# CamelDox_Sch.net
KiCad netlist of a schematic drawn in EAGLE
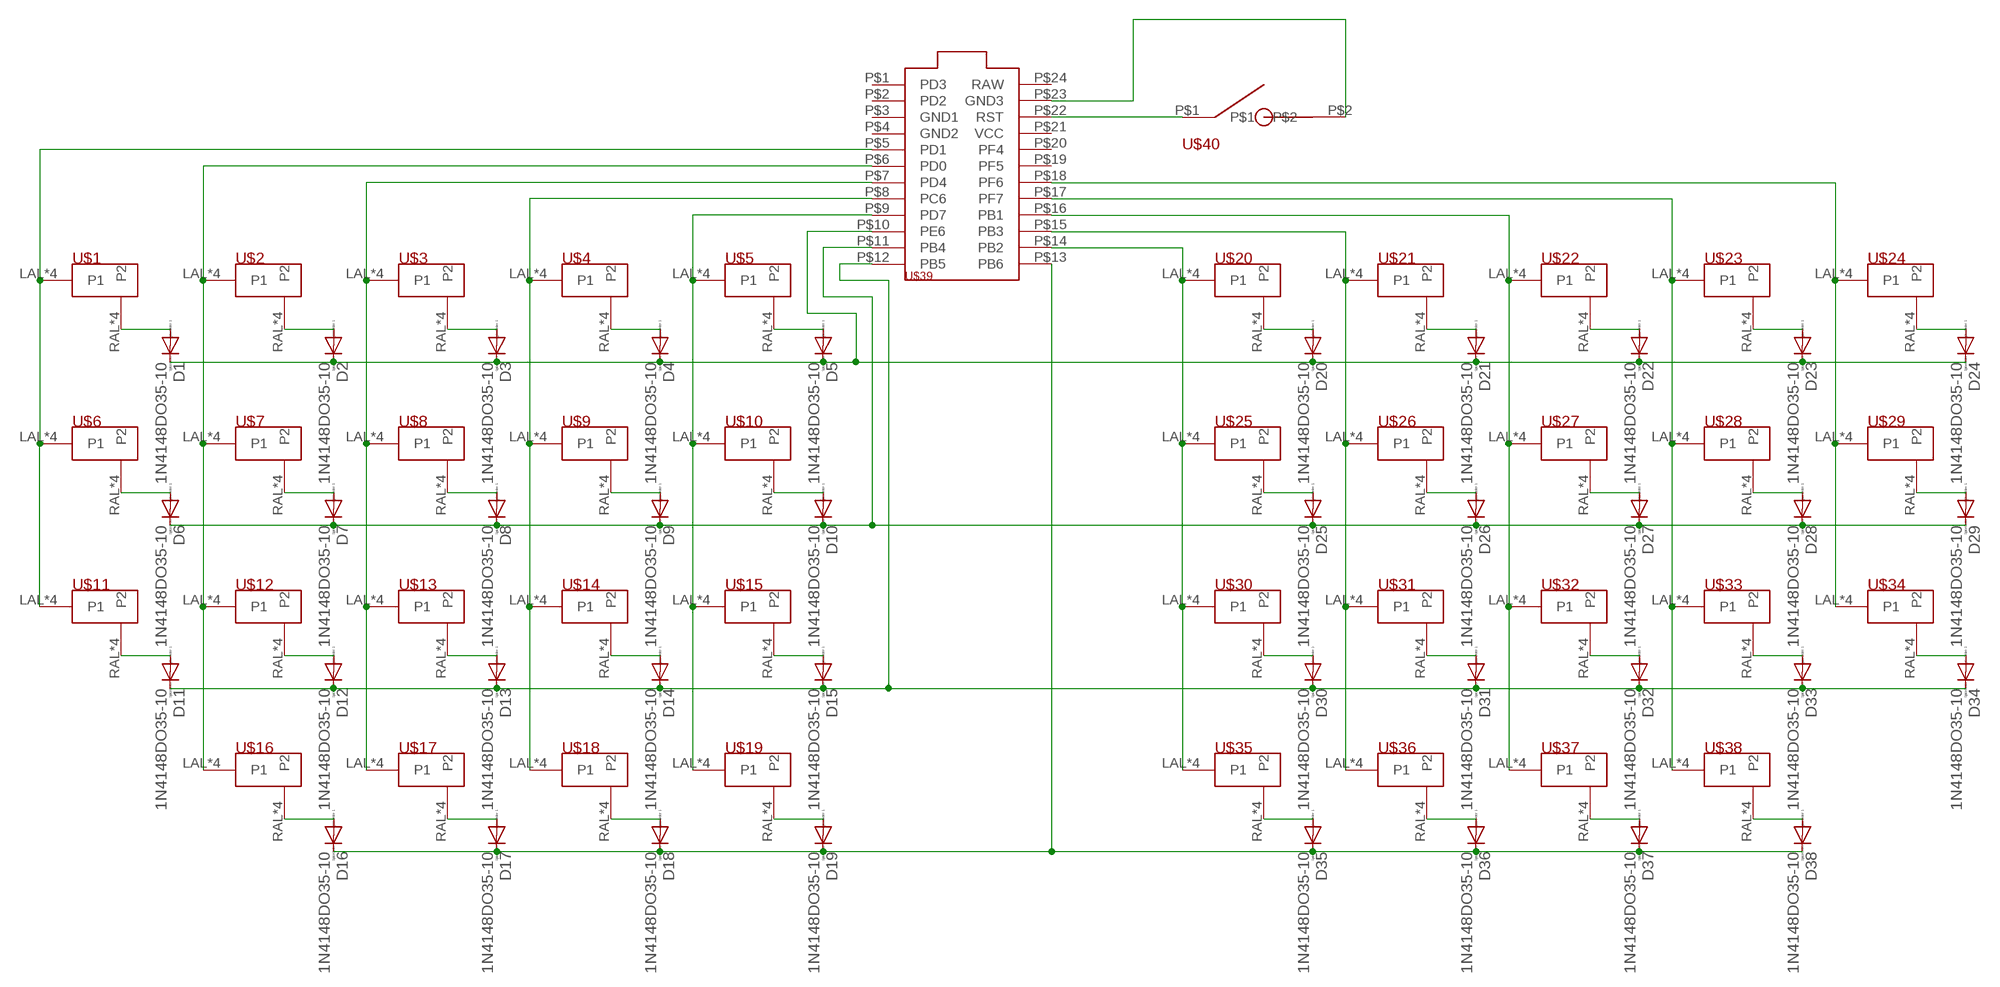
[diagram p0: schematic, sheet 1]

(export (version "E")
  (design (tool "Eeschema 10.0.6"))
  (components
    (comp (ref "D1")
      (value "1N4148DO35-10")
      (footprint "eagle-import:DO35-10")
      (libsource (lib "eagle-import") (part "1N4148DO35-10"))
    )
    (comp (ref "D2")
      (value "1N4148DO35-10")
      (footprint "eagle-import:DO35-10")
      (libsource (lib "eagle-import") (part "1N4148DO35-10"))
    )
    (comp (ref "D3")
      (value "1N4148DO35-10")
      (footprint "eagle-import:DO35-10")
      (libsource (lib "eagle-import") (part "1N4148DO35-10"))
    )
    (comp (ref "D4")
      (value "1N4148DO35-10")
      (footprint "eagle-import:DO35-10")
      (libsource (lib "eagle-import") (part "1N4148DO35-10"))
    )
    (comp (ref "D5")
      (value "1N4148DO35-10")
      (footprint "eagle-import:DO35-10")
      (libsource (lib "eagle-import") (part "1N4148DO35-10"))
    )
    (comp (ref "D6")
      (value "1N4148DO35-10")
      (footprint "eagle-import:DO35-10")
      (libsource (lib "eagle-import") (part "1N4148DO35-10"))
    )
    (comp (ref "D7")
      (value "1N4148DO35-10")
      (footprint "eagle-import:DO35-10")
      (libsource (lib "eagle-import") (part "1N4148DO35-10"))
    )
    (comp (ref "D8")
      (value "1N4148DO35-10")
      (footprint "eagle-import:DO35-10")
      (libsource (lib "eagle-import") (part "1N4148DO35-10"))
    )
    (comp (ref "D9")
      (value "1N4148DO35-10")
      (footprint "eagle-import:DO35-10")
      (libsource (lib "eagle-import") (part "1N4148DO35-10"))
    )
    (comp (ref "D10")
      (value "1N4148DO35-10")
      (footprint "eagle-import:DO35-10")
      (libsource (lib "eagle-import") (part "1N4148DO35-10"))
    )
    (comp (ref "D11")
      (value "1N4148DO35-10")
      (footprint "eagle-import:DO35-10")
      (libsource (lib "eagle-import") (part "1N4148DO35-10"))
    )
    (comp (ref "D12")
      (value "1N4148DO35-10")
      (footprint "eagle-import:DO35-10")
      (libsource (lib "eagle-import") (part "1N4148DO35-10"))
    )
    (comp (ref "D13")
      (value "1N4148DO35-10")
      (footprint "eagle-import:DO35-10")
      (libsource (lib "eagle-import") (part "1N4148DO35-10"))
    )
    (comp (ref "D14")
      (value "1N4148DO35-10")
      (footprint "eagle-import:DO35-10")
      (libsource (lib "eagle-import") (part "1N4148DO35-10"))
    )
    (comp (ref "D15")
      (value "1N4148DO35-10")
      (footprint "eagle-import:DO35-10")
      (libsource (lib "eagle-import") (part "1N4148DO35-10"))
    )
    (comp (ref "D16")
      (value "1N4148DO35-10")
      (footprint "eagle-import:DO35-10")
      (libsource (lib "eagle-import") (part "1N4148DO35-10"))
    )
    (comp (ref "D17")
      (value "1N4148DO35-10")
      (footprint "eagle-import:DO35-10")
      (libsource (lib "eagle-import") (part "1N4148DO35-10"))
    )
    (comp (ref "D18")
      (value "1N4148DO35-10")
      (footprint "eagle-import:DO35-10")
      (libsource (lib "eagle-import") (part "1N4148DO35-10"))
    )
    (comp (ref "D19")
      (value "1N4148DO35-10")
      (footprint "eagle-import:DO35-10")
      (libsource (lib "eagle-import") (part "1N4148DO35-10"))
    )
    (comp (ref "D20")
      (value "1N4148DO35-10")
      (footprint "eagle-import:DO35-10")
      (libsource (lib "eagle-import") (part "1N4148DO35-10"))
    )
    (comp (ref "D21")
      (value "1N4148DO35-10")
      (footprint "eagle-import:DO35-10")
      (libsource (lib "eagle-import") (part "1N4148DO35-10"))
    )
    (comp (ref "D22")
      (value "1N4148DO35-10")
      (footprint "eagle-import:DO35-10")
      (libsource (lib "eagle-import") (part "1N4148DO35-10"))
    )
    (comp (ref "D23")
      (value "1N4148DO35-10")
      (footprint "eagle-import:DO35-10")
      (libsource (lib "eagle-import") (part "1N4148DO35-10"))
    )
    (comp (ref "D24")
      (value "1N4148DO35-10")
      (footprint "eagle-import:DO35-10")
      (libsource (lib "eagle-import") (part "1N4148DO35-10"))
    )
    (comp (ref "D25")
      (value "1N4148DO35-10")
      (footprint "eagle-import:DO35-10")
      (libsource (lib "eagle-import") (part "1N4148DO35-10"))
    )
    (comp (ref "D26")
      (value "1N4148DO35-10")
      (footprint "eagle-import:DO35-10")
      (libsource (lib "eagle-import") (part "1N4148DO35-10"))
    )
    (comp (ref "D27")
      (value "1N4148DO35-10")
      (footprint "eagle-import:DO35-10")
      (libsource (lib "eagle-import") (part "1N4148DO35-10"))
    )
    (comp (ref "D28")
      (value "1N4148DO35-10")
      (footprint "eagle-import:DO35-10")
      (libsource (lib "eagle-import") (part "1N4148DO35-10"))
    )
    (comp (ref "D29")
      (value "1N4148DO35-10")
      (footprint "eagle-import:DO35-10")
      (libsource (lib "eagle-import") (part "1N4148DO35-10"))
    )
    (comp (ref "D30")
      (value "1N4148DO35-10")
      (footprint "eagle-import:DO35-10")
      (libsource (lib "eagle-import") (part "1N4148DO35-10"))
    )
    (comp (ref "D31")
      (value "1N4148DO35-10")
      (footprint "eagle-import:DO35-10")
      (libsource (lib "eagle-import") (part "1N4148DO35-10"))
    )
    (comp (ref "D32")
      (value "1N4148DO35-10")
      (footprint "eagle-import:DO35-10")
      (libsource (lib "eagle-import") (part "1N4148DO35-10"))
    )
    (comp (ref "D33")
      (value "1N4148DO35-10")
      (footprint "eagle-import:DO35-10")
      (libsource (lib "eagle-import") (part "1N4148DO35-10"))
    )
    (comp (ref "D34")
      (value "1N4148DO35-10")
      (footprint "eagle-import:DO35-10")
      (libsource (lib "eagle-import") (part "1N4148DO35-10"))
    )
    (comp (ref "D35")
      (value "1N4148DO35-10")
      (footprint "eagle-import:DO35-10")
      (libsource (lib "eagle-import") (part "1N4148DO35-10"))
    )
    (comp (ref "D36")
      (value "1N4148DO35-10")
      (footprint "eagle-import:DO35-10")
      (libsource (lib "eagle-import") (part "1N4148DO35-10"))
    )
    (comp (ref "D37")
      (value "1N4148DO35-10")
      (footprint "eagle-import:DO35-10")
      (libsource (lib "eagle-import") (part "1N4148DO35-10"))
    )
    (comp (ref "D38")
      (value "1N4148DO35-10")
      (footprint "eagle-import:DO35-10")
      (libsource (lib "eagle-import") (part "1N4148DO35-10"))
    )
    (comp (ref "U$1")
      (value "MANDOUBLEONESIDED")
      (footprint "eagle-import:MX_ALPS")
      (libsource (lib "eagle-import") (part "MANDOUBLEONESIDED"))
    )
    (comp (ref "U$2")
      (value "MANDOUBLEONESIDED")
      (footprint "eagle-import:MX_ALPS")
      (libsource (lib "eagle-import") (part "MANDOUBLEONESIDED"))
    )
    (comp (ref "U$3")
      (value "MANDOUBLEONESIDED")
      (footprint "eagle-import:MX_ALPS")
      (libsource (lib "eagle-import") (part "MANDOUBLEONESIDED"))
    )
    (comp (ref "U$4")
      (value "MANDOUBLEONESIDED")
      (footprint "eagle-import:MX_ALPS")
      (libsource (lib "eagle-import") (part "MANDOUBLEONESIDED"))
    )
    (comp (ref "U$5")
      (value "MANDOUBLEONESIDED")
      (footprint "eagle-import:MX_ALPS")
      (libsource (lib "eagle-import") (part "MANDOUBLEONESIDED"))
    )
    (comp (ref "U$6")
      (value "MANDOUBLEONESIDED")
      (footprint "eagle-import:MX_ALPS")
      (libsource (lib "eagle-import") (part "MANDOUBLEONESIDED"))
    )
    (comp (ref "U$7")
      (value "MANDOUBLEONESIDED")
      (footprint "eagle-import:MX_ALPS")
      (libsource (lib "eagle-import") (part "MANDOUBLEONESIDED"))
    )
    (comp (ref "U$8")
      (value "MANDOUBLEONESIDED")
      (footprint "eagle-import:MX_ALPS")
      (libsource (lib "eagle-import") (part "MANDOUBLEONESIDED"))
    )
    (comp (ref "U$9")
      (value "MANDOUBLEONESIDED")
      (footprint "eagle-import:MX_ALPS")
      (libsource (lib "eagle-import") (part "MANDOUBLEONESIDED"))
    )
    (comp (ref "U$10")
      (value "MANDOUBLEONESIDED")
      (footprint "eagle-import:MX_ALPS")
      (libsource (lib "eagle-import") (part "MANDOUBLEONESIDED"))
    )
    (comp (ref "U$11")
      (value "MANDOUBLEONESIDED")
      (footprint "eagle-import:MX_ALPS")
      (libsource (lib "eagle-import") (part "MANDOUBLEONESIDED"))
    )
    (comp (ref "U$12")
      (value "MANDOUBLEONESIDED")
      (footprint "eagle-import:MX_ALPS")
      (libsource (lib "eagle-import") (part "MANDOUBLEONESIDED"))
    )
    (comp (ref "U$13")
      (value "MANDOUBLEONESIDED")
      (footprint "eagle-import:MX_ALPS")
      (libsource (lib "eagle-import") (part "MANDOUBLEONESIDED"))
    )
    (comp (ref "U$14")
      (value "MANDOUBLEONESIDED")
      (footprint "eagle-import:MX_ALPS")
      (libsource (lib "eagle-import") (part "MANDOUBLEONESIDED"))
    )
    (comp (ref "U$15")
      (value "MANDOUBLEONESIDED")
      (footprint "eagle-import:MX_ALPS")
      (libsource (lib "eagle-import") (part "MANDOUBLEONESIDED"))
    )
    (comp (ref "U$16")
      (value "MANDOUBLEONESIDED")
      (footprint "eagle-import:MX_ALPS")
      (libsource (lib "eagle-import") (part "MANDOUBLEONESIDED"))
    )
    (comp (ref "U$17")
      (value "MANDOUBLEONESIDED")
      (footprint "eagle-import:MX_ALPS")
      (libsource (lib "eagle-import") (part "MANDOUBLEONESIDED"))
    )
    (comp (ref "U$18")
      (value "MANDOUBLEONESIDED")
      (footprint "eagle-import:MX_ALPS")
      (libsource (lib "eagle-import") (part "MANDOUBLEONESIDED"))
    )
    (comp (ref "U$19")
      (value "MANDOUBLEONESIDED")
      (footprint "eagle-import:MX_ALPS")
      (libsource (lib "eagle-import") (part "MANDOUBLEONESIDED"))
    )
    (comp (ref "U$20")
      (value "MANDOUBLEONESIDED")
      (footprint "eagle-import:MX_ALPS")
      (libsource (lib "eagle-import") (part "MANDOUBLEONESIDED"))
    )
    (comp (ref "U$21")
      (value "MANDOUBLEONESIDED")
      (footprint "eagle-import:MX_ALPS")
      (libsource (lib "eagle-import") (part "MANDOUBLEONESIDED"))
    )
    (comp (ref "U$22")
      (value "MANDOUBLEONESIDED")
      (footprint "eagle-import:MX_ALPS")
      (libsource (lib "eagle-import") (part "MANDOUBLEONESIDED"))
    )
    (comp (ref "U$23")
      (value "MANDOUBLEONESIDED")
      (footprint "eagle-import:MX_ALPS")
      (libsource (lib "eagle-import") (part "MANDOUBLEONESIDED"))
    )
    (comp (ref "U$24")
      (value "MANDOUBLEONESIDED")
      (footprint "eagle-import:MX_ALPS")
      (libsource (lib "eagle-import") (part "MANDOUBLEONESIDED"))
    )
    (comp (ref "U$25")
      (value "MANDOUBLEONESIDED")
      (footprint "eagle-import:MX_ALPS")
      (libsource (lib "eagle-import") (part "MANDOUBLEONESIDED"))
    )
    (comp (ref "U$26")
      (value "MANDOUBLEONESIDED")
      (footprint "eagle-import:MX_ALPS")
      (libsource (lib "eagle-import") (part "MANDOUBLEONESIDED"))
    )
    (comp (ref "U$27")
      (value "MANDOUBLEONESIDED")
      (footprint "eagle-import:MX_ALPS")
      (libsource (lib "eagle-import") (part "MANDOUBLEONESIDED"))
    )
    (comp (ref "U$28")
      (value "MANDOUBLEONESIDED")
      (footprint "eagle-import:MX_ALPS")
      (libsource (lib "eagle-import") (part "MANDOUBLEONESIDED"))
    )
    (comp (ref "U$29")
      (value "MANDOUBLEONESIDED")
      (footprint "eagle-import:MX_ALPS")
      (libsource (lib "eagle-import") (part "MANDOUBLEONESIDED"))
    )
    (comp (ref "U$30")
      (value "MANDOUBLEONESIDED")
      (footprint "eagle-import:MX_ALPS")
      (libsource (lib "eagle-import") (part "MANDOUBLEONESIDED"))
    )
    (comp (ref "U$31")
      (value "MANDOUBLEONESIDED")
      (footprint "eagle-import:MX_ALPS")
      (libsource (lib "eagle-import") (part "MANDOUBLEONESIDED"))
    )
    (comp (ref "U$32")
      (value "MANDOUBLEONESIDED")
      (footprint "eagle-import:MX_ALPS")
      (libsource (lib "eagle-import") (part "MANDOUBLEONESIDED"))
    )
    (comp (ref "U$33")
      (value "MANDOUBLEONESIDED")
      (footprint "eagle-import:MX_ALPS")
      (libsource (lib "eagle-import") (part "MANDOUBLEONESIDED"))
    )
    (comp (ref "U$34")
      (value "MANDOUBLEONESIDED")
      (footprint "eagle-import:MX_ALPS")
      (libsource (lib "eagle-import") (part "MANDOUBLEONESIDED"))
    )
    (comp (ref "U$35")
      (value "MANDOUBLEONESIDED")
      (footprint "eagle-import:MX_ALPS")
      (libsource (lib "eagle-import") (part "MANDOUBLEONESIDED"))
    )
    (comp (ref "U$36")
      (value "MANDOUBLEONESIDED")
      (footprint "eagle-import:MX_ALPS")
      (libsource (lib "eagle-import") (part "MANDOUBLEONESIDED"))
    )
    (comp (ref "U$37")
      (value "MANDOUBLEONESIDED")
      (footprint "eagle-import:MX_ALPS")
      (libsource (lib "eagle-import") (part "MANDOUBLEONESIDED"))
    )
    (comp (ref "U$38")
      (value "MANDOUBLEONESIDED")
      (footprint "eagle-import:MX_ALPS")
      (libsource (lib "eagle-import") (part "MANDOUBLEONESIDED"))
    )
    (comp (ref "U$39")
      (value "PROMICRO")
      (footprint "eagle-import:PROMICRO")
      (libsource (lib "eagle-import") (part "PROMICRO"))
    )
    (comp (ref "U$40")
      (value "RSTSW")
      (footprint "eagle-import:SKHL")
      (libsource (lib "eagle-import") (part "RSTSW"))
    )
  )
  (nets
    (net (code "1") (name "Net-(D1-PadA)") (class "Default")
      (node (ref "D1") (pin "A") (pinfunction "A_A") (pintype "passive"))
      (node (ref "U$1") (pin "RAL") (pinfunction "P2_RAL") (pintype "bidirectional"))
      (node (ref "U$1") (pin "RAR") (pinfunction "P2_RAR") (pintype "bidirectional"))
      (node (ref "U$1") (pin "RCL") (pinfunction "P2_RCL") (pintype "bidirectional"))
      (node (ref "U$1") (pin "RCR") (pinfunction "P2_RCR") (pintype "bidirectional"))
    )
    (net (code "2") (name "Net-(D2-PadA)") (class "Default")
      (node (ref "D2") (pin "A") (pinfunction "A_A") (pintype "passive"))
      (node (ref "U$2") (pin "RAL") (pinfunction "P2_RAL") (pintype "bidirectional"))
      (node (ref "U$2") (pin "RAR") (pinfunction "P2_RAR") (pintype "bidirectional"))
      (node (ref "U$2") (pin "RCL") (pinfunction "P2_RCL") (pintype "bidirectional"))
      (node (ref "U$2") (pin "RCR") (pinfunction "P2_RCR") (pintype "bidirectional"))
    )
    (net (code "3") (name "Net-(D3-PadA)") (class "Default")
      (node (ref "D3") (pin "A") (pinfunction "A_A") (pintype "passive"))
      (node (ref "U$3") (pin "RAL") (pinfunction "P2_RAL") (pintype "bidirectional"))
      (node (ref "U$3") (pin "RAR") (pinfunction "P2_RAR") (pintype "bidirectional"))
      (node (ref "U$3") (pin "RCL") (pinfunction "P2_RCL") (pintype "bidirectional"))
      (node (ref "U$3") (pin "RCR") (pinfunction "P2_RCR") (pintype "bidirectional"))
    )
    (net (code "4") (name "Net-(D4-PadA)") (class "Default")
      (node (ref "D4") (pin "A") (pinfunction "A_A") (pintype "passive"))
      (node (ref "U$4") (pin "RAL") (pinfunction "P2_RAL") (pintype "bidirectional"))
      (node (ref "U$4") (pin "RAR") (pinfunction "P2_RAR") (pintype "bidirectional"))
      (node (ref "U$4") (pin "RCL") (pinfunction "P2_RCL") (pintype "bidirectional"))
      (node (ref "U$4") (pin "RCR") (pinfunction "P2_RCR") (pintype "bidirectional"))
    )
    (net (code "5") (name "Net-(D5-PadA)") (class "Default")
      (node (ref "D5") (pin "A") (pinfunction "A_A") (pintype "passive"))
      (node (ref "U$5") (pin "RAL") (pinfunction "P2_RAL") (pintype "bidirectional"))
      (node (ref "U$5") (pin "RAR") (pinfunction "P2_RAR") (pintype "bidirectional"))
      (node (ref "U$5") (pin "RCL") (pinfunction "P2_RCL") (pintype "bidirectional"))
      (node (ref "U$5") (pin "RCR") (pinfunction "P2_RCR") (pintype "bidirectional"))
    )
    (net (code "6") (name "Net-(D6-PadA)") (class "Default")
      (node (ref "D6") (pin "A") (pinfunction "A_A") (pintype "passive"))
      (node (ref "U$6") (pin "RAL") (pinfunction "P2_RAL") (pintype "bidirectional"))
      (node (ref "U$6") (pin "RAR") (pinfunction "P2_RAR") (pintype "bidirectional"))
      (node (ref "U$6") (pin "RCL") (pinfunction "P2_RCL") (pintype "bidirectional"))
      (node (ref "U$6") (pin "RCR") (pinfunction "P2_RCR") (pintype "bidirectional"))
    )
    (net (code "7") (name "Net-(D7-PadA)") (class "Default")
      (node (ref "D7") (pin "A") (pinfunction "A_A") (pintype "passive"))
      (node (ref "U$7") (pin "RAL") (pinfunction "P2_RAL") (pintype "bidirectional"))
      (node (ref "U$7") (pin "RAR") (pinfunction "P2_RAR") (pintype "bidirectional"))
      (node (ref "U$7") (pin "RCL") (pinfunction "P2_RCL") (pintype "bidirectional"))
      (node (ref "U$7") (pin "RCR") (pinfunction "P2_RCR") (pintype "bidirectional"))
    )
    (net (code "8") (name "Net-(D8-PadA)") (class "Default")
      (node (ref "D8") (pin "A") (pinfunction "A_A") (pintype "passive"))
      (node (ref "U$8") (pin "RAL") (pinfunction "P2_RAL") (pintype "bidirectional"))
      (node (ref "U$8") (pin "RAR") (pinfunction "P2_RAR") (pintype "bidirectional"))
      (node (ref "U$8") (pin "RCL") (pinfunction "P2_RCL") (pintype "bidirectional"))
      (node (ref "U$8") (pin "RCR") (pinfunction "P2_RCR") (pintype "bidirectional"))
    )
    (net (code "9") (name "Net-(D9-PadA)") (class "Default")
      (node (ref "D9") (pin "A") (pinfunction "A_A") (pintype "passive"))
      (node (ref "U$9") (pin "RAL") (pinfunction "P2_RAL") (pintype "bidirectional"))
      (node (ref "U$9") (pin "RAR") (pinfunction "P2_RAR") (pintype "bidirectional"))
      (node (ref "U$9") (pin "RCL") (pinfunction "P2_RCL") (pintype "bidirectional"))
      (node (ref "U$9") (pin "RCR") (pinfunction "P2_RCR") (pintype "bidirectional"))
    )
    (net (code "10") (name "Net-(D10-PadA)") (class "Default")
      (node (ref "D10") (pin "A") (pinfunction "A_A") (pintype "passive"))
      (node (ref "U$10") (pin "RAL") (pinfunction "P2_RAL") (pintype "bidirectional"))
      (node (ref "U$10") (pin "RAR") (pinfunction "P2_RAR") (pintype "bidirectional"))
      (node (ref "U$10") (pin "RCL") (pinfunction "P2_RCL") (pintype "bidirectional"))
      (node (ref "U$10") (pin "RCR") (pinfunction "P2_RCR") (pintype "bidirectional"))
    )
    (net (code "11") (name "Net-(D11-PadA)") (class "Default")
      (node (ref "D11") (pin "A") (pinfunction "A_A") (pintype "passive"))
      (node (ref "U$11") (pin "RAL") (pinfunction "P2_RAL") (pintype "bidirectional"))
      (node (ref "U$11") (pin "RAR") (pinfunction "P2_RAR") (pintype "bidirectional"))
      (node (ref "U$11") (pin "RCL") (pinfunction "P2_RCL") (pintype "bidirectional"))
      (node (ref "U$11") (pin "RCR") (pinfunction "P2_RCR") (pintype "bidirectional"))
    )
    (net (code "12") (name "Net-(D12-PadA)") (class "Default")
      (node (ref "D12") (pin "A") (pinfunction "A_A") (pintype "passive"))
      (node (ref "U$12") (pin "RAL") (pinfunction "P2_RAL") (pintype "bidirectional"))
      (node (ref "U$12") (pin "RAR") (pinfunction "P2_RAR") (pintype "bidirectional"))
      (node (ref "U$12") (pin "RCL") (pinfunction "P2_RCL") (pintype "bidirectional"))
      (node (ref "U$12") (pin "RCR") (pinfunction "P2_RCR") (pintype "bidirectional"))
    )
    (net (code "13") (name "Net-(D13-PadA)") (class "Default")
      (node (ref "D13") (pin "A") (pinfunction "A_A") (pintype "passive"))
      (node (ref "U$13") (pin "RAL") (pinfunction "P2_RAL") (pintype "bidirectional"))
      (node (ref "U$13") (pin "RAR") (pinfunction "P2_RAR") (pintype "bidirectional"))
      (node (ref "U$13") (pin "RCL") (pinfunction "P2_RCL") (pintype "bidirectional"))
      (node (ref "U$13") (pin "RCR") (pinfunction "P2_RCR") (pintype "bidirectional"))
    )
    (net (code "14") (name "Net-(D14-PadA)") (class "Default")
      (node (ref "D14") (pin "A") (pinfunction "A_A") (pintype "passive"))
      (node (ref "U$14") (pin "RAL") (pinfunction "P2_RAL") (pintype "bidirectional"))
      (node (ref "U$14") (pin "RAR") (pinfunction "P2_RAR") (pintype "bidirectional"))
      (node (ref "U$14") (pin "RCL") (pinfunction "P2_RCL") (pintype "bidirectional"))
      (node (ref "U$14") (pin "RCR") (pinfunction "P2_RCR") (pintype "bidirectional"))
    )
    (net (code "15") (name "Net-(D15-PadA)") (class "Default")
      (node (ref "D15") (pin "A") (pinfunction "A_A") (pintype "passive"))
      (node (ref "U$15") (pin "RAL") (pinfunction "P2_RAL") (pintype "bidirectional"))
      (node (ref "U$15") (pin "RAR") (pinfunction "P2_RAR") (pintype "bidirectional"))
      (node (ref "U$15") (pin "RCL") (pinfunction "P2_RCL") (pintype "bidirectional"))
      (node (ref "U$15") (pin "RCR") (pinfunction "P2_RCR") (pintype "bidirectional"))
    )
    (net (code "16") (name "Net-(D16-PadA)") (class "Default")
      (node (ref "D16") (pin "A") (pinfunction "A_A") (pintype "passive"))
      (node (ref "U$16") (pin "RAL") (pinfunction "P2_RAL") (pintype "bidirectional"))
      (node (ref "U$16") (pin "RAR") (pinfunction "P2_RAR") (pintype "bidirectional"))
      (node (ref "U$16") (pin "RCL") (pinfunction "P2_RCL") (pintype "bidirectional"))
      (node (ref "U$16") (pin "RCR") (pinfunction "P2_RCR") (pintype "bidirectional"))
    )
    (net (code "17") (name "Net-(D17-PadA)") (class "Default")
      (node (ref "D17") (pin "A") (pinfunction "A_A") (pintype "passive"))
      (node (ref "U$17") (pin "RAL") (pinfunction "P2_RAL") (pintype "bidirectional"))
      (node (ref "U$17") (pin "RAR") (pinfunction "P2_RAR") (pintype "bidirectional"))
      (node (ref "U$17") (pin "RCL") (pinfunction "P2_RCL") (pintype "bidirectional"))
      (node (ref "U$17") (pin "RCR") (pinfunction "P2_RCR") (pintype "bidirectional"))
    )
    (net (code "18") (name "Net-(D18-PadA)") (class "Default")
      (node (ref "D18") (pin "A") (pinfunction "A_A") (pintype "passive"))
      (node (ref "U$18") (pin "RAL") (pinfunction "P2_RAL") (pintype "bidirectional"))
      (node (ref "U$18") (pin "RAR") (pinfunction "P2_RAR") (pintype "bidirectional"))
      (node (ref "U$18") (pin "RCL") (pinfunction "P2_RCL") (pintype "bidirectional"))
      (node (ref "U$18") (pin "RCR") (pinfunction "P2_RCR") (pintype "bidirectional"))
    )
    (net (code "19") (name "Net-(D19-PadA)") (class "Default")
      (node (ref "D19") (pin "A") (pinfunction "A_A") (pintype "passive"))
      (node (ref "U$19") (pin "RAL") (pinfunction "P2_RAL") (pintype "bidirectional"))
      (node (ref "U$19") (pin "RAR") (pinfunction "P2_RAR") (pintype "bidirectional"))
      (node (ref "U$19") (pin "RCL") (pinfunction "P2_RCL") (pintype "bidirectional"))
      (node (ref "U$19") (pin "RCR") (pinfunction "P2_RCR") (pintype "bidirectional"))
    )
    (net (code "20") (name "Net-(D20-PadA)") (class "Default")
      (node (ref "D20") (pin "A") (pinfunction "A_A") (pintype "passive"))
      (node (ref "U$20") (pin "RAL") (pinfunction "P2_RAL") (pintype "bidirectional"))
      (node (ref "U$20") (pin "RAR") (pinfunction "P2_RAR") (pintype "bidirectional"))
      (node (ref "U$20") (pin "RCL") (pinfunction "P2_RCL") (pintype "bidirectional"))
      (node (ref "U$20") (pin "RCR") (pinfunction "P2_RCR") (pintype "bidirectional"))
    )
    (net (code "21") (name "Net-(D21-PadA)") (class "Default")
      (node (ref "D21") (pin "A") (pinfunction "A_A") (pintype "passive"))
      (node (ref "U$21") (pin "RAL") (pinfunction "P2_RAL") (pintype "bidirectional"))
      (node (ref "U$21") (pin "RAR") (pinfunction "P2_RAR") (pintype "bidirectional"))
      (node (ref "U$21") (pin "RCL") (pinfunction "P2_RCL") (pintype "bidirectional"))
      (node (ref "U$21") (pin "RCR") (pinfunction "P2_RCR") (pintype "bidirectional"))
    )
    (net (code "22") (name "Net-(D22-PadA)") (class "Default")
      (node (ref "D22") (pin "A") (pinfunction "A_A") (pintype "passive"))
      (node (ref "U$22") (pin "RAL") (pinfunction "P2_RAL") (pintype "bidirectional"))
      (node (ref "U$22") (pin "RAR") (pinfunction "P2_RAR") (pintype "bidirectional"))
      (node (ref "U$22") (pin "RCL") (pinfunction "P2_RCL") (pintype "bidirectional"))
      (node (ref "U$22") (pin "RCR") (pinfunction "P2_RCR") (pintype "bidirectional"))
    )
    (net (code "23") (name "Net-(D23-PadA)") (class "Default")
      (node (ref "D23") (pin "A") (pinfunction "A_A") (pintype "passive"))
      (node (ref "U$23") (pin "RAL") (pinfunction "P2_RAL") (pintype "bidirectional"))
      (node (ref "U$23") (pin "RAR") (pinfunction "P2_RAR") (pintype "bidirectional"))
      (node (ref "U$23") (pin "RCL") (pinfunction "P2_RCL") (pintype "bidirectional"))
      (node (ref "U$23") (pin "RCR") (pinfunction "P2_RCR") (pintype "bidirectional"))
    )
    (net (code "24") (name "Net-(D24-PadA)") (class "Default")
      (node (ref "D24") (pin "A") (pinfunction "A_A") (pintype "passive"))
      (node (ref "U$24") (pin "RAL") (pinfunction "P2_RAL") (pintype "bidirectional"))
      (node (ref "U$24") (pin "RAR") (pinfunction "P2_RAR") (pintype "bidirectional"))
      (node (ref "U$24") (pin "RCL") (pinfunction "P2_RCL") (pintype "bidirectional"))
      (node (ref "U$24") (pin "RCR") (pinfunction "P2_RCR") (pintype "bidirectional"))
    )
    (net (code "25") (name "Net-(D25-PadA)") (class "Default")
      (node (ref "D25") (pin "A") (pinfunction "A_A") (pintype "passive"))
      (node (ref "U$25") (pin "RAL") (pinfunction "P2_RAL") (pintype "bidirectional"))
      (node (ref "U$25") (pin "RAR") (pinfunction "P2_RAR") (pintype "bidirectional"))
      (node (ref "U$25") (pin "RCL") (pinfunction "P2_RCL") (pintype "bidirectional"))
      (node (ref "U$25") (pin "RCR") (pinfunction "P2_RCR") (pintype "bidirectional"))
    )
    (net (code "26") (name "Net-(D26-PadA)") (class "Default")
      (node (ref "D26") (pin "A") (pinfunction "A_A") (pintype "passive"))
      (node (ref "U$26") (pin "RAL") (pinfunction "P2_RAL") (pintype "bidirectional"))
      (node (ref "U$26") (pin "RAR") (pinfunction "P2_RAR") (pintype "bidirectional"))
      (node (ref "U$26") (pin "RCL") (pinfunction "P2_RCL") (pintype "bidirectional"))
      (node (ref "U$26") (pin "RCR") (pinfunction "P2_RCR") (pintype "bidirectional"))
    )
    (net (code "27") (name "Net-(D27-PadA)") (class "Default")
      (node (ref "D27") (pin "A") (pinfunction "A_A") (pintype "passive"))
      (node (ref "U$27") (pin "RAL") (pinfunction "P2_RAL") (pintype "bidirectional"))
      (node (ref "U$27") (pin "RAR") (pinfunction "P2_RAR") (pintype "bidirectional"))
      (node (ref "U$27") (pin "RCL") (pinfunction "P2_RCL") (pintype "bidirectional"))
      (node (ref "U$27") (pin "RCR") (pinfunction "P2_RCR") (pintype "bidirectional"))
    )
    (net (code "28") (name "Net-(D28-PadA)") (class "Default")
      (node (ref "D28") (pin "A") (pinfunction "A_A") (pintype "passive"))
      (node (ref "U$28") (pin "RAL") (pinfunction "P2_RAL") (pintype "bidirectional"))
      (node (ref "U$28") (pin "RAR") (pinfunction "P2_RAR") (pintype "bidirectional"))
      (node (ref "U$28") (pin "RCL") (pinfunction "P2_RCL") (pintype "bidirectional"))
      (node (ref "U$28") (pin "RCR") (pinfunction "P2_RCR") (pintype "bidirectional"))
    )
    (net (code "29") (name "Net-(D29-PadA)") (class "Default")
      (node (ref "D29") (pin "A") (pinfunction "A_A") (pintype "passive"))
      (node (ref "U$29") (pin "RAL") (pinfunction "P2_RAL") (pintype "bidirectional"))
      (node (ref "U$29") (pin "RAR") (pinfunction "P2_RAR") (pintype "bidirectional"))
      (node (ref "U$29") (pin "RCL") (pinfunction "P2_RCL") (pintype "bidirectional"))
      (node (ref "U$29") (pin "RCR") (pinfunction "P2_RCR") (pintype "bidirectional"))
    )
    (net (code "30") (name "Net-(D30-PadA)") (class "Default")
      (node (ref "D30") (pin "A") (pinfunction "A_A") (pintype "passive"))
      (node (ref "U$30") (pin "RAL") (pinfunction "P2_RAL") (pintype "bidirectional"))
      (node (ref "U$30") (pin "RAR") (pinfunction "P2_RAR") (pintype "bidirectional"))
      (node (ref "U$30") (pin "RCL") (pinfunction "P2_RCL") (pintype "bidirectional"))
      (node (ref "U$30") (pin "RCR") (pinfunction "P2_RCR") (pintype "bidirectional"))
    )
    (net (code "31") (name "Net-(D31-PadA)") (class "Default")
      (node (ref "D31") (pin "A") (pinfunction "A_A") (pintype "passive"))
      (node (ref "U$31") (pin "RAL") (pinfunction "P2_RAL") (pintype "bidirectional"))
      (node (ref "U$31") (pin "RAR") (pinfunction "P2_RAR") (pintype "bidirectional"))
      (node (ref "U$31") (pin "RCL") (pinfunction "P2_RCL") (pintype "bidirectional"))
      (node (ref "U$31") (pin "RCR") (pinfunction "P2_RCR") (pintype "bidirectional"))
    )
    (net (code "32") (name "Net-(D32-PadA)") (class "Default")
      (node (ref "D32") (pin "A") (pinfunction "A_A") (pintype "passive"))
      (node (ref "U$32") (pin "RAL") (pinfunction "P2_RAL") (pintype "bidirectional"))
      (node (ref "U$32") (pin "RAR") (pinfunction "P2_RAR") (pintype "bidirectional"))
      (node (ref "U$32") (pin "RCL") (pinfunction "P2_RCL") (pintype "bidirectional"))
      (node (ref "U$32") (pin "RCR") (pinfunction "P2_RCR") (pintype "bidirectional"))
    )
    (net (code "33") (name "Net-(D33-PadA)") (class "Default")
      (node (ref "D33") (pin "A") (pinfunction "A_A") (pintype "passive"))
      (node (ref "U$33") (pin "RAL") (pinfunction "P2_RAL") (pintype "bidirectional"))
      (node (ref "U$33") (pin "RAR") (pinfunction "P2_RAR") (pintype "bidirectional"))
      (node (ref "U$33") (pin "RCL") (pinfunction "P2_RCL") (pintype "bidirectional"))
      (node (ref "U$33") (pin "RCR") (pinfunction "P2_RCR") (pintype "bidirectional"))
    )
    (net (code "34") (name "Net-(D34-PadA)") (class "Default")
      (node (ref "D34") (pin "A") (pinfunction "A_A") (pintype "passive"))
      (node (ref "U$34") (pin "RAL") (pinfunction "P2_RAL") (pintype "bidirectional"))
      (node (ref "U$34") (pin "RAR") (pinfunction "P2_RAR") (pintype "bidirectional"))
      (node (ref "U$34") (pin "RCL") (pinfunction "P2_RCL") (pintype "bidirectional"))
      (node (ref "U$34") (pin "RCR") (pinfunction "P2_RCR") (pintype "bidirectional"))
    )
    (net (code "35") (name "Net-(D35-PadA)") (class "Default")
      (node (ref "D35") (pin "A") (pinfunction "A_A") (pintype "passive"))
      (node (ref "U$35") (pin "RAL") (pinfunction "P2_RAL") (pintype "bidirectional"))
      (node (ref "U$35") (pin "RAR") (pinfunction "P2_RAR") (pintype "bidirectional"))
      (node (ref "U$35") (pin "RCL") (pinfunction "P2_RCL") (pintype "bidirectional"))
      (node (ref "U$35") (pin "RCR") (pinfunction "P2_RCR") (pintype "bidirectional"))
    )
    (net (code "36") (name "Net-(D36-PadA)") (class "Default")
      (node (ref "D36") (pin "A") (pinfunction "A_A") (pintype "passive"))
      (node (ref "U$36") (pin "RAL") (pinfunction "P2_RAL") (pintype "bidirectional"))
      (node (ref "U$36") (pin "RAR") (pinfunction "P2_RAR") (pintype "bidirectional"))
      (node (ref "U$36") (pin "RCL") (pinfunction "P2_RCL") (pintype "bidirectional"))
      (node (ref "U$36") (pin "RCR") (pinfunction "P2_RCR") (pintype "bidirectional"))
    )
    (net (code "37") (name "Net-(D37-PadA)") (class "Default")
      (node (ref "D37") (pin "A") (pinfunction "A_A") (pintype "passive"))
      (node (ref "U$37") (pin "RAL") (pinfunction "P2_RAL") (pintype "bidirectional"))
      (node (ref "U$37") (pin "RAR") (pinfunction "P2_RAR") (pintype "bidirectional"))
      (node (ref "U$37") (pin "RCL") (pinfunction "P2_RCL") (pintype "bidirectional"))
      (node (ref "U$37") (pin "RCR") (pinfunction "P2_RCR") (pintype "bidirectional"))
    )
    (net (code "38") (name "Net-(D38-PadA)") (class "Default")
      (node (ref "D38") (pin "A") (pinfunction "A_A") (pintype "passive"))
      (node (ref "U$38") (pin "RAL") (pinfunction "P2_RAL") (pintype "bidirectional"))
      (node (ref "U$38") (pin "RAR") (pinfunction "P2_RAR") (pintype "bidirectional"))
      (node (ref "U$38") (pin "RCL") (pinfunction "P2_RCL") (pintype "bidirectional"))
      (node (ref "U$38") (pin "RCR") (pinfunction "P2_RCR") (pintype "bidirectional"))
    )
    (net (code "39") (name "Net-(U$39-GND3)") (class "Default")
      (node (ref "U$39") (pin "P$23") (pinfunction "GND3_P$23") (pintype "bidirectional"))
      (node (ref "U$40") (pin "P$2") (pinfunction "P$2_P$2") (pintype "bidirectional"))
    )
    (net (code "40") (name "Net-(U$39-PB1)") (class "Default")
      (node (ref "U$22") (pin "LAL") (pinfunction "P1_LAL") (pintype "bidirectional"))
      (node (ref "U$22") (pin "LAR") (pinfunction "P1_LAR") (pintype "bidirectional"))
      (node (ref "U$22") (pin "LCL") (pinfunction "P1_LCL") (pintype "bidirectional"))
      (node (ref "U$22") (pin "LCR") (pinfunction "P1_LCR") (pintype "bidirectional"))
      (node (ref "U$27") (pin "LAL") (pinfunction "P1_LAL") (pintype "bidirectional"))
      (node (ref "U$27") (pin "LAR") (pinfunction "P1_LAR") (pintype "bidirectional"))
      (node (ref "U$27") (pin "LCL") (pinfunction "P1_LCL") (pintype "bidirectional"))
      (node (ref "U$27") (pin "LCR") (pinfunction "P1_LCR") (pintype "bidirectional"))
      (node (ref "U$32") (pin "LAL") (pinfunction "P1_LAL") (pintype "bidirectional"))
      (node (ref "U$32") (pin "LAR") (pinfunction "P1_LAR") (pintype "bidirectional"))
      (node (ref "U$32") (pin "LCL") (pinfunction "P1_LCL") (pintype "bidirectional"))
      (node (ref "U$32") (pin "LCR") (pinfunction "P1_LCR") (pintype "bidirectional"))
      (node (ref "U$37") (pin "LAL") (pinfunction "P1_LAL") (pintype "bidirectional"))
      (node (ref "U$37") (pin "LAR") (pinfunction "P1_LAR") (pintype "bidirectional"))
      (node (ref "U$37") (pin "LCL") (pinfunction "P1_LCL") (pintype "bidirectional"))
      (node (ref "U$37") (pin "LCR") (pinfunction "P1_LCR") (pintype "bidirectional"))
      (node (ref "U$39") (pin "P$16") (pinfunction "PB1_P$16") (pintype "bidirectional"))
    )
    (net (code "41") (name "Net-(U$39-PB2)") (class "Default")
      (node (ref "U$20") (pin "LAL") (pinfunction "P1_LAL") (pintype "bidirectional"))
      (node (ref "U$20") (pin "LAR") (pinfunction "P1_LAR") (pintype "bidirectional"))
      (node (ref "U$20") (pin "LCL") (pinfunction "P1_LCL") (pintype "bidirectional"))
      (node (ref "U$20") (pin "LCR") (pinfunction "P1_LCR") (pintype "bidirectional"))
      (node (ref "U$25") (pin "LAL") (pinfunction "P1_LAL") (pintype "bidirectional"))
      (node (ref "U$25") (pin "LAR") (pinfunction "P1_LAR") (pintype "bidirectional"))
      (node (ref "U$25") (pin "LCL") (pinfunction "P1_LCL") (pintype "bidirectional"))
      (node (ref "U$25") (pin "LCR") (pinfunction "P1_LCR") (pintype "bidirectional"))
      (node (ref "U$30") (pin "LAL") (pinfunction "P1_LAL") (pintype "bidirectional"))
      (node (ref "U$30") (pin "LAR") (pinfunction "P1_LAR") (pintype "bidirectional"))
      (node (ref "U$30") (pin "LCL") (pinfunction "P1_LCL") (pintype "bidirectional"))
      (node (ref "U$30") (pin "LCR") (pinfunction "P1_LCR") (pintype "bidirectional"))
      (node (ref "U$35") (pin "LAL") (pinfunction "P1_LAL") (pintype "bidirectional"))
      (node (ref "U$35") (pin "LAR") (pinfunction "P1_LAR") (pintype "bidirectional"))
      (node (ref "U$35") (pin "LCL") (pinfunction "P1_LCL") (pintype "bidirectional"))
      (node (ref "U$35") (pin "LCR") (pinfunction "P1_LCR") (pintype "bidirectional"))
      (node (ref "U$39") (pin "P$14") (pinfunction "PB2_P$14") (pintype "bidirectional"))
    )
    (net (code "42") (name "Net-(U$39-PB3)") (class "Default")
      (node (ref "U$21") (pin "LAL") (pinfunction "P1_LAL") (pintype "bidirectional"))
      (node (ref "U$21") (pin "LAR") (pinfunction "P1_LAR") (pintype "bidirectional"))
      (node (ref "U$21") (pin "LCL") (pinfunction "P1_LCL") (pintype "bidirectional"))
      (node (ref "U$21") (pin "LCR") (pinfunction "P1_LCR") (pintype "bidirectional"))
      (node (ref "U$26") (pin "LAL") (pinfunction "P1_LAL") (pintype "bidirectional"))
      (node (ref "U$26") (pin "LAR") (pinfunction "P1_LAR") (pintype "bidirectional"))
      (node (ref "U$26") (pin "LCL") (pinfunction "P1_LCL") (pintype "bidirectional"))
      (node (ref "U$26") (pin "LCR") (pinfunction "P1_LCR") (pintype "bidirectional"))
      (node (ref "U$31") (pin "LAL") (pinfunction "P1_LAL") (pintype "bidirectional"))
      (node (ref "U$31") (pin "LAR") (pinfunction "P1_LAR") (pintype "bidirectional"))
      (node (ref "U$31") (pin "LCL") (pinfunction "P1_LCL") (pintype "bidirectional"))
      (node (ref "U$31") (pin "LCR") (pinfunction "P1_LCR") (pintype "bidirectional"))
      (node (ref "U$36") (pin "LAL") (pinfunction "P1_LAL") (pintype "bidirectional"))
      (node (ref "U$36") (pin "LAR") (pinfunction "P1_LAR") (pintype "bidirectional"))
      (node (ref "U$36") (pin "LCL") (pinfunction "P1_LCL") (pintype "bidirectional"))
      (node (ref "U$36") (pin "LCR") (pinfunction "P1_LCR") (pintype "bidirectional"))
      (node (ref "U$39") (pin "P$15") (pinfunction "PB3_P$15") (pintype "bidirectional"))
    )
    (net (code "43") (name "Net-(U$39-PB4)") (class "Default")
      (node (ref "D10") (pin "C") (pinfunction "C_C") (pintype "passive"))
      (node (ref "D25") (pin "C") (pinfunction "C_C") (pintype "passive"))
      (node (ref "D26") (pin "C") (pinfunction "C_C") (pintype "passive"))
      (node (ref "D27") (pin "C") (pinfunction "C_C") (pintype "passive"))
      (node (ref "D28") (pin "C") (pinfunction "C_C") (pintype "passive"))
      (node (ref "D29") (pin "C") (pinfunction "C_C") (pintype "passive"))
      (node (ref "D6") (pin "C") (pinfunction "C_C") (pintype "passive"))
      (node (ref "D7") (pin "C") (pinfunction "C_C") (pintype "passive"))
      (node (ref "D8") (pin "C") (pinfunction "C_C") (pintype "passive"))
      (node (ref "D9") (pin "C") (pinfunction "C_C") (pintype "passive"))
      (node (ref "U$39") (pin "P$11") (pinfunction "PB4_P$11") (pintype "bidirectional"))
    )
    (net (code "44") (name "Net-(U$39-PB5)") (class "Default")
      (node (ref "D11") (pin "C") (pinfunction "C_C") (pintype "passive"))
      (node (ref "D12") (pin "C") (pinfunction "C_C") (pintype "passive"))
      (node (ref "D13") (pin "C") (pinfunction "C_C") (pintype "passive"))
      (node (ref "D14") (pin "C") (pinfunction "C_C") (pintype "passive"))
      (node (ref "D15") (pin "C") (pinfunction "C_C") (pintype "passive"))
      (node (ref "D30") (pin "C") (pinfunction "C_C") (pintype "passive"))
      (node (ref "D31") (pin "C") (pinfunction "C_C") (pintype "passive"))
      (node (ref "D32") (pin "C") (pinfunction "C_C") (pintype "passive"))
      (node (ref "D33") (pin "C") (pinfunction "C_C") (pintype "passive"))
      (node (ref "D34") (pin "C") (pinfunction "C_C") (pintype "passive"))
      (node (ref "U$39") (pin "P$12") (pinfunction "PB5_P$12") (pintype "bidirectional"))
    )
    (net (code "45") (name "Net-(U$39-PB6)") (class "Default")
      (node (ref "D16") (pin "C") (pinfunction "C_C") (pintype "passive"))
      (node (ref "D17") (pin "C") (pinfunction "C_C") (pintype "passive"))
      (node (ref "D18") (pin "C") (pinfunction "C_C") (pintype "passive"))
      (node (ref "D19") (pin "C") (pinfunction "C_C") (pintype "passive"))
      (node (ref "D35") (pin "C") (pinfunction "C_C") (pintype "passive"))
      (node (ref "D36") (pin "C") (pinfunction "C_C") (pintype "passive"))
      (node (ref "D37") (pin "C") (pinfunction "C_C") (pintype "passive"))
      (node (ref "D38") (pin "C") (pinfunction "C_C") (pintype "passive"))
      (node (ref "U$39") (pin "P$13") (pinfunction "PB6_P$13") (pintype "bidirectional"))
    )
    (net (code "46") (name "Net-(U$39-PC6)") (class "Default")
      (node (ref "U$14") (pin "LAL") (pinfunction "P1_LAL") (pintype "bidirectional"))
      (node (ref "U$14") (pin "LAR") (pinfunction "P1_LAR") (pintype "bidirectional"))
      (node (ref "U$14") (pin "LCL") (pinfunction "P1_LCL") (pintype "bidirectional"))
      (node (ref "U$14") (pin "LCR") (pinfunction "P1_LCR") (pintype "bidirectional"))
      (node (ref "U$18") (pin "LAL") (pinfunction "P1_LAL") (pintype "bidirectional"))
      (node (ref "U$18") (pin "LAR") (pinfunction "P1_LAR") (pintype "bidirectional"))
      (node (ref "U$18") (pin "LCL") (pinfunction "P1_LCL") (pintype "bidirectional"))
      (node (ref "U$18") (pin "LCR") (pinfunction "P1_LCR") (pintype "bidirectional"))
      (node (ref "U$39") (pin "P$8") (pinfunction "PC6_P$8") (pintype "bidirectional"))
      (node (ref "U$4") (pin "LAL") (pinfunction "P1_LAL") (pintype "bidirectional"))
      (node (ref "U$4") (pin "LAR") (pinfunction "P1_LAR") (pintype "bidirectional"))
      (node (ref "U$4") (pin "LCL") (pinfunction "P1_LCL") (pintype "bidirectional"))
      (node (ref "U$4") (pin "LCR") (pinfunction "P1_LCR") (pintype "bidirectional"))
      (node (ref "U$9") (pin "LAL") (pinfunction "P1_LAL") (pintype "bidirectional"))
      (node (ref "U$9") (pin "LAR") (pinfunction "P1_LAR") (pintype "bidirectional"))
      (node (ref "U$9") (pin "LCL") (pinfunction "P1_LCL") (pintype "bidirectional"))
      (node (ref "U$9") (pin "LCR") (pinfunction "P1_LCR") (pintype "bidirectional"))
    )
    (net (code "47") (name "Net-(U$39-PD0)") (class "Default")
      (node (ref "U$12") (pin "LAL") (pinfunction "P1_LAL") (pintype "bidirectional"))
      (node (ref "U$12") (pin "LAR") (pinfunction "P1_LAR") (pintype "bidirectional"))
      (node (ref "U$12") (pin "LCL") (pinfunction "P1_LCL") (pintype "bidirectional"))
      (node (ref "U$12") (pin "LCR") (pinfunction "P1_LCR") (pintype "bidirectional"))
      (node (ref "U$16") (pin "LAL") (pinfunction "P1_LAL") (pintype "bidirectional"))
      (node (ref "U$16") (pin "LAR") (pinfunction "P1_LAR") (pintype "bidirectional"))
      (node (ref "U$16") (pin "LCL") (pinfunction "P1_LCL") (pintype "bidirectional"))
      (node (ref "U$16") (pin "LCR") (pinfunction "P1_LCR") (pintype "bidirectional"))
      (node (ref "U$2") (pin "LAL") (pinfunction "P1_LAL") (pintype "bidirectional"))
      (node (ref "U$2") (pin "LAR") (pinfunction "P1_LAR") (pintype "bidirectional"))
      (node (ref "U$2") (pin "LCL") (pinfunction "P1_LCL") (pintype "bidirectional"))
      (node (ref "U$2") (pin "LCR") (pinfunction "P1_LCR") (pintype "bidirectional"))
      (node (ref "U$39") (pin "P$6") (pinfunction "PD0_P$6") (pintype "bidirectional"))
      (node (ref "U$7") (pin "LAL") (pinfunction "P1_LAL") (pintype "bidirectional"))
      (node (ref "U$7") (pin "LAR") (pinfunction "P1_LAR") (pintype "bidirectional"))
      (node (ref "U$7") (pin "LCL") (pinfunction "P1_LCL") (pintype "bidirectional"))
      (node (ref "U$7") (pin "LCR") (pinfunction "P1_LCR") (pintype "bidirectional"))
    )
    (net (code "48") (name "Net-(U$39-PD1)") (class "Default")
      (node (ref "U$1") (pin "LAL") (pinfunction "P1_LAL") (pintype "bidirectional"))
      (node (ref "U$1") (pin "LAR") (pinfunction "P1_LAR") (pintype "bidirectional"))
      (node (ref "U$1") (pin "LCL") (pinfunction "P1_LCL") (pintype "bidirectional"))
      (node (ref "U$1") (pin "LCR") (pinfunction "P1_LCR") (pintype "bidirectional"))
      (node (ref "U$11") (pin "LAL") (pinfunction "P1_LAL") (pintype "bidirectional"))
      (node (ref "U$11") (pin "LAR") (pinfunction "P1_LAR") (pintype "bidirectional"))
      (node (ref "U$11") (pin "LCL") (pinfunction "P1_LCL") (pintype "bidirectional"))
      (node (ref "U$11") (pin "LCR") (pinfunction "P1_LCR") (pintype "bidirectional"))
      (node (ref "U$39") (pin "P$5") (pinfunction "PD1_P$5") (pintype "bidirectional"))
      (node (ref "U$6") (pin "LAL") (pinfunction "P1_LAL") (pintype "bidirectional"))
      (node (ref "U$6") (pin "LAR") (pinfunction "P1_LAR") (pintype "bidirectional"))
      (node (ref "U$6") (pin "LCL") (pinfunction "P1_LCL") (pintype "bidirectional"))
      (node (ref "U$6") (pin "LCR") (pinfunction "P1_LCR") (pintype "bidirectional"))
    )
    (net (code "49") (name "Net-(U$39-PD4)") (class "Default")
      (node (ref "U$13") (pin "LAL") (pinfunction "P1_LAL") (pintype "bidirectional"))
      (node (ref "U$13") (pin "LAR") (pinfunction "P1_LAR") (pintype "bidirectional"))
      (node (ref "U$13") (pin "LCL") (pinfunction "P1_LCL") (pintype "bidirectional"))
      (node (ref "U$13") (pin "LCR") (pinfunction "P1_LCR") (pintype "bidirectional"))
      (node (ref "U$17") (pin "LAL") (pinfunction "P1_LAL") (pintype "bidirectional"))
      (node (ref "U$17") (pin "LAR") (pinfunction "P1_LAR") (pintype "bidirectional"))
      (node (ref "U$17") (pin "LCL") (pinfunction "P1_LCL") (pintype "bidirectional"))
      (node (ref "U$17") (pin "LCR") (pinfunction "P1_LCR") (pintype "bidirectional"))
      (node (ref "U$3") (pin "LAL") (pinfunction "P1_LAL") (pintype "bidirectional"))
      (node (ref "U$3") (pin "LAR") (pinfunction "P1_LAR") (pintype "bidirectional"))
      (node (ref "U$3") (pin "LCL") (pinfunction "P1_LCL") (pintype "bidirectional"))
      (node (ref "U$3") (pin "LCR") (pinfunction "P1_LCR") (pintype "bidirectional"))
      (node (ref "U$39") (pin "P$7") (pinfunction "PD4_P$7") (pintype "bidirectional"))
      (node (ref "U$8") (pin "LAL") (pinfunction "P1_LAL") (pintype "bidirectional"))
      (node (ref "U$8") (pin "LAR") (pinfunction "P1_LAR") (pintype "bidirectional"))
      (node (ref "U$8") (pin "LCL") (pinfunction "P1_LCL") (pintype "bidirectional"))
      (node (ref "U$8") (pin "LCR") (pinfunction "P1_LCR") (pintype "bidirectional"))
    )
    (net (code "50") (name "Net-(U$39-PD7)") (class "Default")
      (node (ref "U$10") (pin "LAL") (pinfunction "P1_LAL") (pintype "bidirectional"))
      (node (ref "U$10") (pin "LAR") (pinfunction "P1_LAR") (pintype "bidirectional"))
      (node (ref "U$10") (pin "LCL") (pinfunction "P1_LCL") (pintype "bidirectional"))
      (node (ref "U$10") (pin "LCR") (pinfunction "P1_LCR") (pintype "bidirectional"))
      (node (ref "U$15") (pin "LAL") (pinfunction "P1_LAL") (pintype "bidirectional"))
      (node (ref "U$15") (pin "LAR") (pinfunction "P1_LAR") (pintype "bidirectional"))
      (node (ref "U$15") (pin "LCL") (pinfunction "P1_LCL") (pintype "bidirectional"))
      (node (ref "U$15") (pin "LCR") (pinfunction "P1_LCR") (pintype "bidirectional"))
      (node (ref "U$19") (pin "LAL") (pinfunction "P1_LAL") (pintype "bidirectional"))
      (node (ref "U$19") (pin "LAR") (pinfunction "P1_LAR") (pintype "bidirectional"))
      (node (ref "U$19") (pin "LCL") (pinfunction "P1_LCL") (pintype "bidirectional"))
      (node (ref "U$19") (pin "LCR") (pinfunction "P1_LCR") (pintype "bidirectional"))
      (node (ref "U$39") (pin "P$9") (pinfunction "PD7_P$9") (pintype "bidirectional"))
      (node (ref "U$5") (pin "LAL") (pinfunction "P1_LAL") (pintype "bidirectional"))
      (node (ref "U$5") (pin "LAR") (pinfunction "P1_LAR") (pintype "bidirectional"))
      (node (ref "U$5") (pin "LCL") (pinfunction "P1_LCL") (pintype "bidirectional"))
      (node (ref "U$5") (pin "LCR") (pinfunction "P1_LCR") (pintype "bidirectional"))
    )
    (net (code "51") (name "Net-(U$39-PE6)") (class "Default")
      (node (ref "D1") (pin "C") (pinfunction "C_C") (pintype "passive"))
      (node (ref "D2") (pin "C") (pinfunction "C_C") (pintype "passive"))
      (node (ref "D20") (pin "C") (pinfunction "C_C") (pintype "passive"))
      (node (ref "D21") (pin "C") (pinfunction "C_C") (pintype "passive"))
      (node (ref "D22") (pin "C") (pinfunction "C_C") (pintype "passive"))
      (node (ref "D23") (pin "C") (pinfunction "C_C") (pintype "passive"))
      (node (ref "D24") (pin "C") (pinfunction "C_C") (pintype "passive"))
      (node (ref "D3") (pin "C") (pinfunction "C_C") (pintype "passive"))
      (node (ref "D4") (pin "C") (pinfunction "C_C") (pintype "passive"))
      (node (ref "D5") (pin "C") (pinfunction "C_C") (pintype "passive"))
      (node (ref "U$39") (pin "P$10") (pinfunction "PE6_P$10") (pintype "bidirectional"))
    )
    (net (code "52") (name "Net-(U$39-PF6)") (class "Default")
      (node (ref "U$24") (pin "LAL") (pinfunction "P1_LAL") (pintype "bidirectional"))
      (node (ref "U$24") (pin "LAR") (pinfunction "P1_LAR") (pintype "bidirectional"))
      (node (ref "U$24") (pin "LCL") (pinfunction "P1_LCL") (pintype "bidirectional"))
      (node (ref "U$24") (pin "LCR") (pinfunction "P1_LCR") (pintype "bidirectional"))
      (node (ref "U$29") (pin "LAL") (pinfunction "P1_LAL") (pintype "bidirectional"))
      (node (ref "U$29") (pin "LAR") (pinfunction "P1_LAR") (pintype "bidirectional"))
      (node (ref "U$29") (pin "LCL") (pinfunction "P1_LCL") (pintype "bidirectional"))
      (node (ref "U$29") (pin "LCR") (pinfunction "P1_LCR") (pintype "bidirectional"))
      (node (ref "U$34") (pin "LAL") (pinfunction "P1_LAL") (pintype "bidirectional"))
      (node (ref "U$34") (pin "LAR") (pinfunction "P1_LAR") (pintype "bidirectional"))
      (node (ref "U$34") (pin "LCL") (pinfunction "P1_LCL") (pintype "bidirectional"))
      (node (ref "U$34") (pin "LCR") (pinfunction "P1_LCR") (pintype "bidirectional"))
      (node (ref "U$39") (pin "P$18") (pinfunction "PF6_P$18") (pintype "bidirectional"))
    )
    (net (code "53") (name "Net-(U$39-PF7)") (class "Default")
      (node (ref "U$23") (pin "LAL") (pinfunction "P1_LAL") (pintype "bidirectional"))
      (node (ref "U$23") (pin "LAR") (pinfunction "P1_LAR") (pintype "bidirectional"))
      (node (ref "U$23") (pin "LCL") (pinfunction "P1_LCL") (pintype "bidirectional"))
      (node (ref "U$23") (pin "LCR") (pinfunction "P1_LCR") (pintype "bidirectional"))
      (node (ref "U$28") (pin "LAL") (pinfunction "P1_LAL") (pintype "bidirectional"))
      (node (ref "U$28") (pin "LAR") (pinfunction "P1_LAR") (pintype "bidirectional"))
      (node (ref "U$28") (pin "LCL") (pinfunction "P1_LCL") (pintype "bidirectional"))
      (node (ref "U$28") (pin "LCR") (pinfunction "P1_LCR") (pintype "bidirectional"))
      (node (ref "U$33") (pin "LAL") (pinfunction "P1_LAL") (pintype "bidirectional"))
      (node (ref "U$33") (pin "LAR") (pinfunction "P1_LAR") (pintype "bidirectional"))
      (node (ref "U$33") (pin "LCL") (pinfunction "P1_LCL") (pintype "bidirectional"))
      (node (ref "U$33") (pin "LCR") (pinfunction "P1_LCR") (pintype "bidirectional"))
      (node (ref "U$38") (pin "LAL") (pinfunction "P1_LAL") (pintype "bidirectional"))
      (node (ref "U$38") (pin "LAR") (pinfunction "P1_LAR") (pintype "bidirectional"))
      (node (ref "U$38") (pin "LCL") (pinfunction "P1_LCL") (pintype "bidirectional"))
      (node (ref "U$38") (pin "LCR") (pinfunction "P1_LCR") (pintype "bidirectional"))
      (node (ref "U$39") (pin "P$17") (pinfunction "PF7_P$17") (pintype "bidirectional"))
    )
    (net (code "54") (name "Net-(U$39-RST)") (class "Default")
      (node (ref "U$39") (pin "P$22") (pinfunction "RST_P$22") (pintype "bidirectional"))
      (node (ref "U$40") (pin "P$1") (pinfunction "P$1_P$1") (pintype "bidirectional"))
    )
    (net (code "55") (name "unconnected-(U$39-GND1-PadP$3)") (class "Default")
      (node (ref "U$39") (pin "P$3") (pinfunction "GND1_P$3") (pintype "bidirectional"))
    )
    (net (code "56") (name "unconnected-(U$39-GND2-PadP$4)") (class "Default")
      (node (ref "U$39") (pin "P$4") (pinfunction "GND2_P$4") (pintype "bidirectional"))
    )
    (net (code "57") (name "unconnected-(U$39-PD2-PadP$2)") (class "Default")
      (node (ref "U$39") (pin "P$2") (pinfunction "PD2_P$2") (pintype "bidirectional"))
    )
    (net (code "58") (name "unconnected-(U$39-PD3-PadP$1)") (class "Default")
      (node (ref "U$39") (pin "P$1") (pinfunction "PD3_P$1") (pintype "bidirectional"))
    )
    (net (code "59") (name "unconnected-(U$39-PF4-PadP$20)") (class "Default")
      (node (ref "U$39") (pin "P$20") (pinfunction "PF4_P$20") (pintype "bidirectional"))
    )
    (net (code "60") (name "unconnected-(U$39-PF5-PadP$19)") (class "Default")
      (node (ref "U$39") (pin "P$19") (pinfunction "PF5_P$19") (pintype "bidirectional"))
    )
    (net (code "61") (name "unconnected-(U$39-RAW-PadP$24)") (class "Default")
      (node (ref "U$39") (pin "P$24") (pinfunction "RAW_P$24") (pintype "bidirectional"))
    )
    (net (code "62") (name "unconnected-(U$39-VCC-PadP$21)") (class "Default")
      (node (ref "U$39") (pin "P$21") (pinfunction "VCC_P$21") (pintype "bidirectional"))
    )
  )
)
